# HLD-stat-tracker-bottom.net
KiCad netlist of a schematic drawn in EAGLE
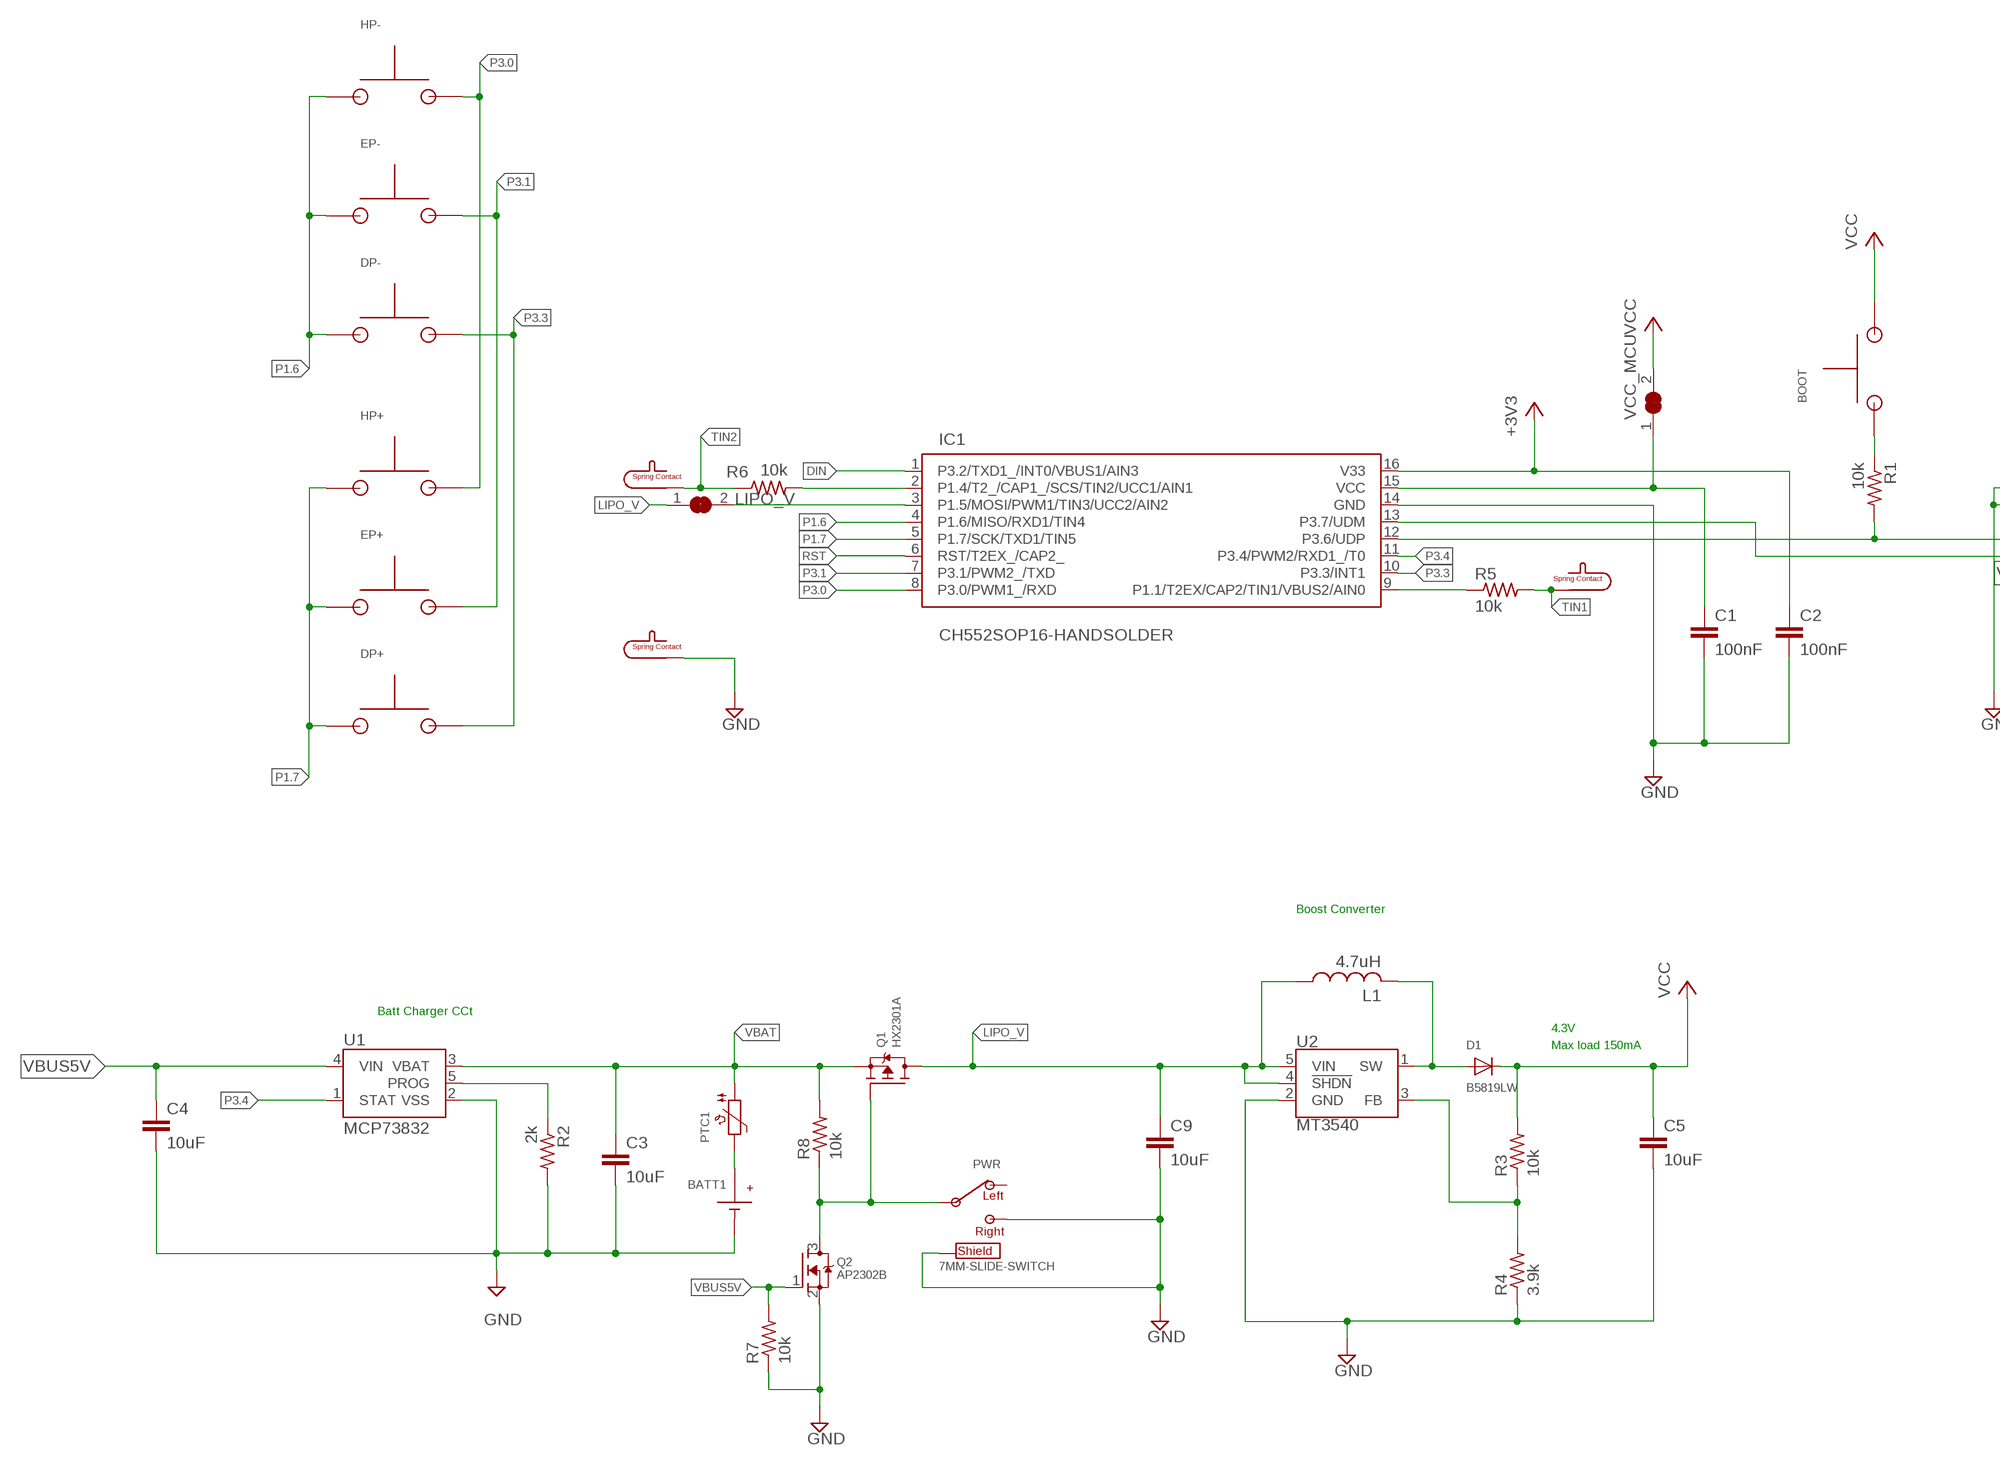
[diagram p0: schematic, sheet 1, part 1 of 2]
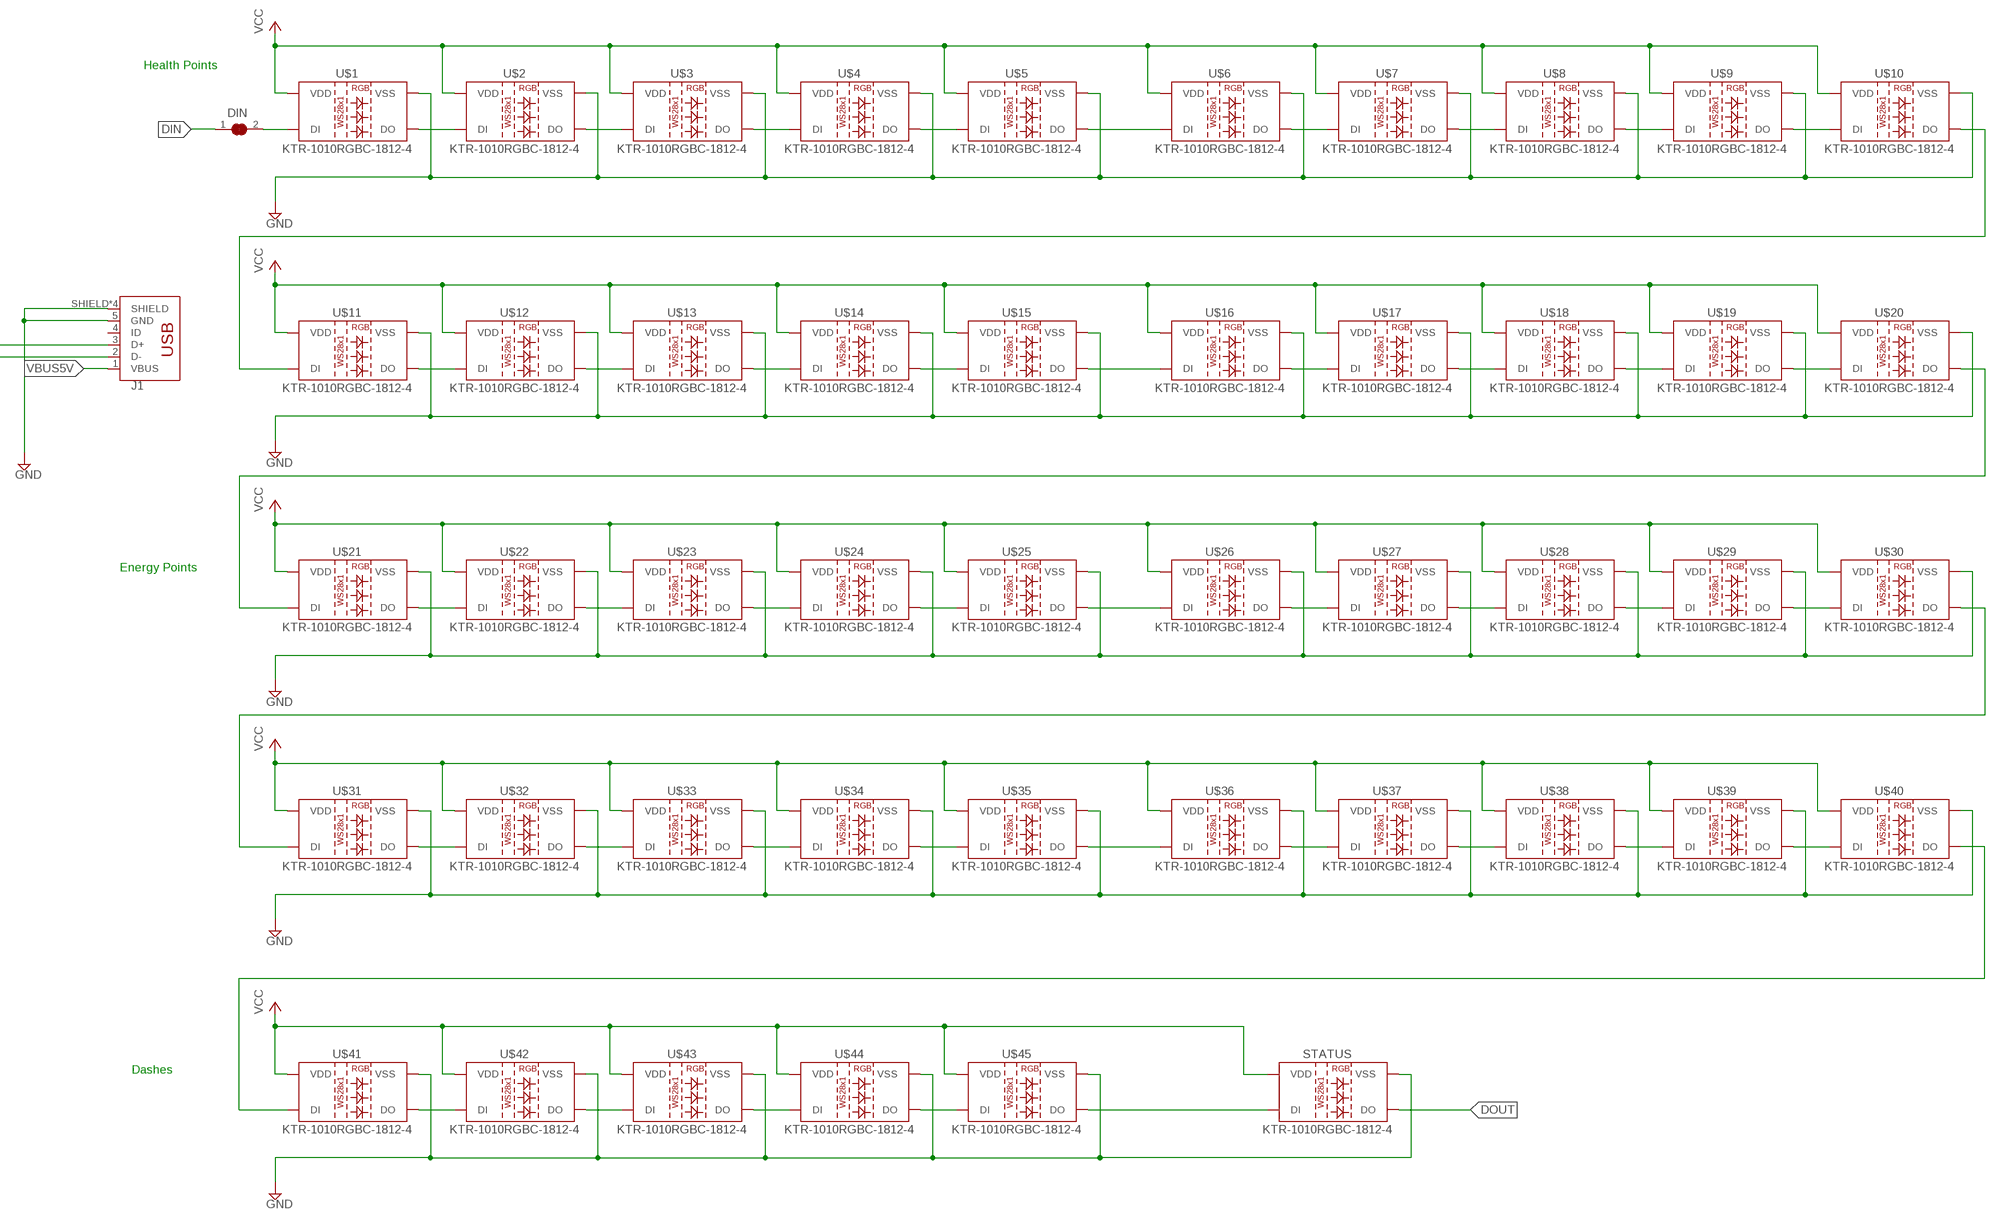
[diagram p1: schematic, sheet 1, part 2 of 2]

(export (version "E")
  (design (tool "Eeschema 10.0.6"))
  (components
    (comp (ref "BATT1")
      (value "BATT+")
      (footprint "eagle-import:BATT+PAD")
      (fields (field (name "PARTNO") "?"))
      (libsource (lib "eagle-import") (part "BATT+"))
    )
    (comp (ref "BATT1-")
      (value "BATT-")
      (footprint "eagle-import:BATT-PAD")
      (fields (field (name "PARTNO") "?"))
      (libsource (lib "eagle-import") (part "BATT-"))
    )
    (comp (ref "BOOT")
      (value "TACTSW")
      (footprint "eagle-import:3MM-TACT")
      (fields (field (name "MANUFACTURER") "SHOU HAN") (field (name "PARTNO") "TS3315A"))
      (libsource (lib "eagle-import") (part "TACTSW"))
    )
    (comp (ref "C1")
      (value "100nF")
      (footprint "eagle-import:C0805K")
      (fields (field (name "PARTNO") "?"))
      (libsource (lib "eagle-import") (part "C-EUC0805K"))
    )
    (comp (ref "C2")
      (value "100nF")
      (footprint "eagle-import:C0805K")
      (fields (field (name "PARTNO") "?"))
      (libsource (lib "eagle-import") (part "C-EUC0805K"))
    )
    (comp (ref "C3")
      (value "10uF")
      (footprint "eagle-import:C0805K")
      (fields (field (name "PARTNO") "?"))
      (libsource (lib "eagle-import") (part "C-EUC0805K"))
    )
    (comp (ref "C4")
      (value "10uF")
      (footprint "eagle-import:C0805K")
      (fields (field (name "PARTNO") "?"))
      (libsource (lib "eagle-import") (part "C-EUC0805K"))
    )
    (comp (ref "C5")
      (value "10uF")
      (footprint "eagle-import:C0805K")
      (fields (field (name "PARTNO") "?"))
      (libsource (lib "eagle-import") (part "C-EUC0805K"))
    )
    (comp (ref "C9")
      (value "10uF")
      (footprint "eagle-import:C0805K")
      (fields (field (name "PARTNO") "?"))
      (libsource (lib "eagle-import") (part "C-EUC0805K"))
    )
    (comp (ref "D1")
      (value "B5819LW")
      (footprint "eagle-import:SOD-123")
      (fields (field (name "MANUFACTURER") "Guangdong Hottech ") (field (name "PARTNO") "B5819LW "))
      (libsource (lib "eagle-import") (part "DIODESOD-123"))
    )
    (comp (ref "DIN")
      (value "SOLDERJUMPER-NC")
      (footprint "eagle-import:SOLDERJUMPER_CLOSEDWIRE_SMALL")
      (libsource (lib "eagle-import") (part "SOLDERJUMPER-NC"))
    )
    (comp (ref "DP+")
      (value "TACTSW")
      (footprint "eagle-import:3MM-TACT")
      (fields (field (name "MANUFACTURER") "SHOU HAN") (field (name "PARTNO") "TS3315A"))
      (libsource (lib "eagle-import") (part "TACTSW"))
    )
    (comp (ref "DP-")
      (value "TACTSW")
      (footprint "eagle-import:3MM-TACT")
      (fields (field (name "MANUFACTURER") "SHOU HAN") (field (name "PARTNO") "TS3315A"))
      (libsource (lib "eagle-import") (part "TACTSW"))
    )
    (comp (ref "EP+")
      (value "TACTSW")
      (footprint "eagle-import:3MM-TACT")
      (fields (field (name "MANUFACTURER") "SHOU HAN") (field (name "PARTNO") "TS3315A"))
      (libsource (lib "eagle-import") (part "TACTSW"))
    )
    (comp (ref "EP-")
      (value "TACTSW")
      (footprint "eagle-import:3MM-TACT")
      (fields (field (name "MANUFACTURER") "SHOU HAN") (field (name "PARTNO") "TS3315A"))
      (libsource (lib "eagle-import") (part "TACTSW"))
    )
    (comp (ref "GND")
      (value "SPRING-CONTACT")
      (footprint "eagle-import:818000905-SPRING-CONTACT")
      (fields (field (name "MANUFACTURER") "ECT") (field (name "PARTNO") "ECT818000905"))
      (libsource (lib "eagle-import") (part "SPRING-CONTACT"))
    )
    (comp (ref "HP+")
      (value "TACTSW")
      (footprint "eagle-import:3MM-TACT")
      (fields (field (name "MANUFACTURER") "SHOU HAN") (field (name "PARTNO") "TS3315A"))
      (libsource (lib "eagle-import") (part "TACTSW"))
    )
    (comp (ref "HP-")
      (value "TACTSW")
      (footprint "eagle-import:3MM-TACT")
      (fields
        (field (name "MANUFACTURER") "SHOU HAN")
        (field (name "PARTNO") "TS3315A")
        (field (name "MANUFACTURER_1") "SHOU HAN")
        (field (name "PARTNO_1") "TS3315A")
      )
      (libsource (lib "eagle-import") (part "TACTSW"))
    )
    (comp (ref "IC1")
      (value "CH552SOP16-HANDSOLDER")
      (footprint "eagle-import:SOP16-HANDSOLDER")
      (fields (field (name "MANUFACTURER") "WCH(Jiangsu Qin Heng)") (field (name "PARTNO") "CH552G"))
      (libsource (lib "eagle-import") (part "CH552SOP16-HANDSOLDER"))
    )
    (comp (ref "J1")
      (value "USB_MICRO-BSINK-PLATE")
      (footprint "eagle-import:USB-B-MICRO-SMD-SINK-PLATE")
      (fields
        (field (name "MANUFACTURER") "Jing Extension of the Electronic Co. ")
        (field (name "PARTNO") "C40957")
      )
      (libsource (lib "eagle-import") (part "USB_MICRO-BSINK-PLATE"))
    )
    (comp (ref "L1")
      (value "4.7uH")
      (footprint "eagle-import:BEADC2012X105N")
      (fields (field (name "MANUFACTURER") "INPAQ") (field (name "PARTNO") "C315723"))
      (libsource (lib "eagle-import") (part "INDUCTOR2012"))
    )
    (comp (ref "LIPO_V")
      (value "SOLDERJUMPER-NC")
      (footprint "eagle-import:SOLDERJUMPER_CLOSEDWIRE_SMALL")
      (libsource (lib "eagle-import") (part "SOLDERJUMPER-NC"))
    )
    (comp (ref "PTC1")
      (value "PTC0805")
      (footprint "eagle-import:WCAP-CSGP_0805_H1.25_R")
      (fields
        (field (name "MANUFACTURER") "  Jinrui Electronic Materials Co.")
        (field (name "PARTNO") "JK-SMD0805-075")
      )
      (libsource (lib "eagle-import") (part "PTC0805"))
    )
    (comp (ref "PWR")
      (value "7MM-SLIDE-SWITCH")
      (footprint "eagle-import:7MM-SMD-SLIDE-SWITCH")
      (fields (field (name "MANUFACTURER") "XKB Enterprise") (field (name "PARTNO") "SK-3296S-01-L1 "))
      (libsource (lib "eagle-import") (part "7MM-SLIDE-SWITCH"))
    )
    (comp (ref "Q1")
      (value "HX2301A")
      (footprint "eagle-import:SOT23-R")
      (fields (field (name "MANUFACTURER") "HX(hengjiaxing) ") (field (name "PARTNO") "HX2301A "))
      (libsource (lib "eagle-import") (part "MOSFET-P"))
    )
    (comp (ref "Q2")
      (value "AP2302B")
      (footprint "eagle-import:SOT23-R")
      (fields (field (name "MANUFACTURER") "HX(hengjiaxing)"))
      (libsource (lib "eagle-import") (part "MOSFET-NREFLOW"))
    )
    (comp (ref "R1")
      (value "10k")
      (footprint "eagle-import:R0805S")
      (fields (field (name "PARTNO") "?"))
      (libsource (lib "eagle-import") (part "R-US_R0805S"))
    )
    (comp (ref "R2")
      (value "2k")
      (footprint "eagle-import:R0805S")
      (fields (field (name "PARTNO") "?"))
      (libsource (lib "eagle-import") (part "R-US_R0805S"))
    )
    (comp (ref "R3")
      (value "10k")
      (footprint "eagle-import:R0805S")
      (fields (field (name "PARTNO") "?"))
      (libsource (lib "eagle-import") (part "R-US_R0805S"))
    )
    (comp (ref "R4")
      (value "3.9k")
      (footprint "eagle-import:R0805S")
      (fields (field (name "PARTNO") "?"))
      (libsource (lib "eagle-import") (part "R-US_R0805S"))
    )
    (comp (ref "R5")
      (value "10k")
      (footprint "eagle-import:R0805S")
      (fields (field (name "PARTNO") "?"))
      (libsource (lib "eagle-import") (part "R-US_R0805S"))
    )
    (comp (ref "R6")
      (value "10k")
      (footprint "eagle-import:R0805S")
      (fields (field (name "PARTNO") "?"))
      (libsource (lib "eagle-import") (part "R-US_R0805S"))
    )
    (comp (ref "R7")
      (value "10k")
      (footprint "eagle-import:R0805S")
      (fields (field (name "PARTNO") "?"))
      (libsource (lib "eagle-import") (part "R-US_R0805S"))
    )
    (comp (ref "R8")
      (value "10k")
      (footprint "eagle-import:R0805S")
      (fields (field (name "PARTNO") "?"))
      (libsource (lib "eagle-import") (part "R-US_R0805S"))
    )
    (comp (ref "STATUS")
      (value "KTR-1010RGBC-1812-4")
      (footprint "eagle-import:SK6812-2020")
      (fields (field (name "MANUFACTURER") "KTRLIGHT"))
      (libsource (lib "eagle-import") (part "KTR-1010RGBC-1812-4"))
    )
    (comp (ref "TIN1")
      (value "SPRING-CONTACT")
      (footprint "eagle-import:818000905-SPRING-CONTACT")
      (fields (field (name "MANUFACTURER") "ECT") (field (name "PARTNO") "ECT818000905"))
      (libsource (lib "eagle-import") (part "SPRING-CONTACT"))
    )
    (comp (ref "TIN2")
      (value "SPRING-CONTACT")
      (footprint "eagle-import:818000905-SPRING-CONTACT")
      (fields (field (name "MANUFACTURER") "ECT") (field (name "PARTNO") "ECT818000905"))
      (libsource (lib "eagle-import") (part "SPRING-CONTACT"))
    )
    (comp (ref "U$1")
      (value "KTR-1010RGBC-1812-4")
      (footprint "eagle-import:SK6812-2020")
      (fields (field (name "MANUFACTURER") "KTRLIGHT"))
      (libsource (lib "eagle-import") (part "KTR-1010RGBC-1812-4"))
    )
    (comp (ref "U$2")
      (value "KTR-1010RGBC-1812-4")
      (footprint "eagle-import:SK6812-2020")
      (fields (field (name "MANUFACTURER") "KTRLIGHT"))
      (libsource (lib "eagle-import") (part "KTR-1010RGBC-1812-4"))
    )
    (comp (ref "U$3")
      (value "KTR-1010RGBC-1812-4")
      (footprint "eagle-import:SK6812-2020")
      (fields (field (name "MANUFACTURER") "KTRLIGHT"))
      (libsource (lib "eagle-import") (part "KTR-1010RGBC-1812-4"))
    )
    (comp (ref "U$4")
      (value "KTR-1010RGBC-1812-4")
      (footprint "eagle-import:SK6812-2020")
      (fields (field (name "MANUFACTURER") "KTRLIGHT"))
      (libsource (lib "eagle-import") (part "KTR-1010RGBC-1812-4"))
    )
    (comp (ref "U$5")
      (value "KTR-1010RGBC-1812-4")
      (footprint "eagle-import:SK6812-2020")
      (fields (field (name "MANUFACTURER") "KTRLIGHT"))
      (libsource (lib "eagle-import") (part "KTR-1010RGBC-1812-4"))
    )
    (comp (ref "U$6")
      (value "KTR-1010RGBC-1812-4")
      (footprint "eagle-import:SK6812-2020")
      (fields (field (name "MANUFACTURER") "KTRLIGHT"))
      (libsource (lib "eagle-import") (part "KTR-1010RGBC-1812-4"))
    )
    (comp (ref "U$7")
      (value "KTR-1010RGBC-1812-4")
      (footprint "eagle-import:SK6812-2020")
      (fields (field (name "MANUFACTURER") "KTRLIGHT"))
      (libsource (lib "eagle-import") (part "KTR-1010RGBC-1812-4"))
    )
    (comp (ref "U$8")
      (value "KTR-1010RGBC-1812-4")
      (footprint "eagle-import:SK6812-2020")
      (fields (field (name "MANUFACTURER") "KTRLIGHT"))
      (libsource (lib "eagle-import") (part "KTR-1010RGBC-1812-4"))
    )
    (comp (ref "U$9")
      (value "KTR-1010RGBC-1812-4")
      (footprint "eagle-import:SK6812-2020")
      (fields (field (name "MANUFACTURER") "KTRLIGHT"))
      (libsource (lib "eagle-import") (part "KTR-1010RGBC-1812-4"))
    )
    (comp (ref "U$10")
      (value "KTR-1010RGBC-1812-4")
      (footprint "eagle-import:SK6812-2020")
      (fields (field (name "MANUFACTURER") "KTRLIGHT"))
      (libsource (lib "eagle-import") (part "KTR-1010RGBC-1812-4"))
    )
    (comp (ref "U$11")
      (value "KTR-1010RGBC-1812-4")
      (footprint "eagle-import:SK6812-2020")
      (fields (field (name "MANUFACTURER") "KTRLIGHT"))
      (libsource (lib "eagle-import") (part "KTR-1010RGBC-1812-4"))
    )
    (comp (ref "U$12")
      (value "KTR-1010RGBC-1812-4")
      (footprint "eagle-import:SK6812-2020")
      (fields (field (name "MANUFACTURER") "KTRLIGHT"))
      (libsource (lib "eagle-import") (part "KTR-1010RGBC-1812-4"))
    )
    (comp (ref "U$13")
      (value "KTR-1010RGBC-1812-4")
      (footprint "eagle-import:SK6812-2020")
      (fields (field (name "MANUFACTURER") "KTRLIGHT"))
      (libsource (lib "eagle-import") (part "KTR-1010RGBC-1812-4"))
    )
    (comp (ref "U$14")
      (value "KTR-1010RGBC-1812-4")
      (footprint "eagle-import:SK6812-2020")
      (fields (field (name "MANUFACTURER") "KTRLIGHT"))
      (libsource (lib "eagle-import") (part "KTR-1010RGBC-1812-4"))
    )
    (comp (ref "U$15")
      (value "KTR-1010RGBC-1812-4")
      (footprint "eagle-import:SK6812-2020")
      (fields (field (name "MANUFACTURER") "KTRLIGHT"))
      (libsource (lib "eagle-import") (part "KTR-1010RGBC-1812-4"))
    )
    (comp (ref "U$16")
      (value "KTR-1010RGBC-1812-4")
      (footprint "eagle-import:SK6812-2020")
      (fields (field (name "MANUFACTURER") "KTRLIGHT"))
      (libsource (lib "eagle-import") (part "KTR-1010RGBC-1812-4"))
    )
    (comp (ref "U$17")
      (value "KTR-1010RGBC-1812-4")
      (footprint "eagle-import:SK6812-2020")
      (fields (field (name "MANUFACTURER") "KTRLIGHT"))
      (libsource (lib "eagle-import") (part "KTR-1010RGBC-1812-4"))
    )
    (comp (ref "U$18")
      (value "KTR-1010RGBC-1812-4")
      (footprint "eagle-import:SK6812-2020")
      (fields (field (name "MANUFACTURER") "KTRLIGHT"))
      (libsource (lib "eagle-import") (part "KTR-1010RGBC-1812-4"))
    )
    (comp (ref "U$19")
      (value "KTR-1010RGBC-1812-4")
      (footprint "eagle-import:SK6812-2020")
      (fields (field (name "MANUFACTURER") "KTRLIGHT"))
      (libsource (lib "eagle-import") (part "KTR-1010RGBC-1812-4"))
    )
    (comp (ref "U$20")
      (value "KTR-1010RGBC-1812-4")
      (footprint "eagle-import:SK6812-2020")
      (fields (field (name "MANUFACTURER") "KTRLIGHT"))
      (libsource (lib "eagle-import") (part "KTR-1010RGBC-1812-4"))
    )
    (comp (ref "U$21")
      (value "KTR-1010RGBC-1812-4")
      (footprint "eagle-import:SK6812-2020")
      (fields (field (name "MANUFACTURER") "KTRLIGHT"))
      (libsource (lib "eagle-import") (part "KTR-1010RGBC-1812-4"))
    )
    (comp (ref "U$22")
      (value "KTR-1010RGBC-1812-4")
      (footprint "eagle-import:SK6812-2020")
      (fields (field (name "MANUFACTURER") "KTRLIGHT"))
      (libsource (lib "eagle-import") (part "KTR-1010RGBC-1812-4"))
    )
    (comp (ref "U$23")
      (value "KTR-1010RGBC-1812-4")
      (footprint "eagle-import:SK6812-2020")
      (fields (field (name "MANUFACTURER") "KTRLIGHT"))
      (libsource (lib "eagle-import") (part "KTR-1010RGBC-1812-4"))
    )
    (comp (ref "U$24")
      (value "KTR-1010RGBC-1812-4")
      (footprint "eagle-import:SK6812-2020")
      (fields (field (name "MANUFACTURER") "KTRLIGHT"))
      (libsource (lib "eagle-import") (part "KTR-1010RGBC-1812-4"))
    )
    (comp (ref "U$25")
      (value "KTR-1010RGBC-1812-4")
      (footprint "eagle-import:SK6812-2020")
      (fields (field (name "MANUFACTURER") "KTRLIGHT"))
      (libsource (lib "eagle-import") (part "KTR-1010RGBC-1812-4"))
    )
    (comp (ref "U$26")
      (value "KTR-1010RGBC-1812-4")
      (footprint "eagle-import:SK6812-2020")
      (fields (field (name "MANUFACTURER") "KTRLIGHT"))
      (libsource (lib "eagle-import") (part "KTR-1010RGBC-1812-4"))
    )
    (comp (ref "U$27")
      (value "KTR-1010RGBC-1812-4")
      (footprint "eagle-import:SK6812-2020")
      (fields (field (name "MANUFACTURER") "KTRLIGHT"))
      (libsource (lib "eagle-import") (part "KTR-1010RGBC-1812-4"))
    )
    (comp (ref "U$28")
      (value "KTR-1010RGBC-1812-4")
      (footprint "eagle-import:SK6812-2020")
      (fields (field (name "MANUFACTURER") "KTRLIGHT"))
      (libsource (lib "eagle-import") (part "KTR-1010RGBC-1812-4"))
    )
    (comp (ref "U$29")
      (value "KTR-1010RGBC-1812-4")
      (footprint "eagle-import:SK6812-2020")
      (fields (field (name "MANUFACTURER") "KTRLIGHT"))
      (libsource (lib "eagle-import") (part "KTR-1010RGBC-1812-4"))
    )
    (comp (ref "U$30")
      (value "KTR-1010RGBC-1812-4")
      (footprint "eagle-import:SK6812-2020")
      (fields (field (name "MANUFACTURER") "KTRLIGHT"))
      (libsource (lib "eagle-import") (part "KTR-1010RGBC-1812-4"))
    )
    (comp (ref "U$31")
      (value "KTR-1010RGBC-1812-4")
      (footprint "eagle-import:SK6812-2020")
      (fields (field (name "MANUFACTURER") "KTRLIGHT"))
      (libsource (lib "eagle-import") (part "KTR-1010RGBC-1812-4"))
    )
    (comp (ref "U$32")
      (value "KTR-1010RGBC-1812-4")
      (footprint "eagle-import:SK6812-2020")
      (fields (field (name "MANUFACTURER") "KTRLIGHT"))
      (libsource (lib "eagle-import") (part "KTR-1010RGBC-1812-4"))
    )
    (comp (ref "U$33")
      (value "KTR-1010RGBC-1812-4")
      (footprint "eagle-import:SK6812-2020")
      (fields (field (name "MANUFACTURER") "KTRLIGHT"))
      (libsource (lib "eagle-import") (part "KTR-1010RGBC-1812-4"))
    )
    (comp (ref "U$34")
      (value "KTR-1010RGBC-1812-4")
      (footprint "eagle-import:SK6812-2020")
      (fields (field (name "MANUFACTURER") "KTRLIGHT"))
      (libsource (lib "eagle-import") (part "KTR-1010RGBC-1812-4"))
    )
    (comp (ref "U$35")
      (value "KTR-1010RGBC-1812-4")
      (footprint "eagle-import:SK6812-2020")
      (fields (field (name "MANUFACTURER") "KTRLIGHT"))
      (libsource (lib "eagle-import") (part "KTR-1010RGBC-1812-4"))
    )
    (comp (ref "U$36")
      (value "KTR-1010RGBC-1812-4")
      (footprint "eagle-import:SK6812-2020")
      (fields (field (name "MANUFACTURER") "KTRLIGHT"))
      (libsource (lib "eagle-import") (part "KTR-1010RGBC-1812-4"))
    )
    (comp (ref "U$37")
      (value "KTR-1010RGBC-1812-4")
      (footprint "eagle-import:SK6812-2020")
      (fields (field (name "MANUFACTURER") "KTRLIGHT"))
      (libsource (lib "eagle-import") (part "KTR-1010RGBC-1812-4"))
    )
    (comp (ref "U$38")
      (value "KTR-1010RGBC-1812-4")
      (footprint "eagle-import:SK6812-2020")
      (fields (field (name "MANUFACTURER") "KTRLIGHT"))
      (libsource (lib "eagle-import") (part "KTR-1010RGBC-1812-4"))
    )
    (comp (ref "U$39")
      (value "KTR-1010RGBC-1812-4")
      (footprint "eagle-import:SK6812-2020")
      (fields (field (name "MANUFACTURER") "KTRLIGHT"))
      (libsource (lib "eagle-import") (part "KTR-1010RGBC-1812-4"))
    )
    (comp (ref "U$40")
      (value "KTR-1010RGBC-1812-4")
      (footprint "eagle-import:SK6812-2020")
      (fields (field (name "MANUFACTURER") "KTRLIGHT"))
      (libsource (lib "eagle-import") (part "KTR-1010RGBC-1812-4"))
    )
    (comp (ref "U$41")
      (value "KTR-1010RGBC-1812-4")
      (footprint "eagle-import:SK6812-2020")
      (fields (field (name "MANUFACTURER") "KTRLIGHT"))
      (libsource (lib "eagle-import") (part "KTR-1010RGBC-1812-4"))
    )
    (comp (ref "U$42")
      (value "KTR-1010RGBC-1812-4")
      (footprint "eagle-import:SK6812-2020")
      (fields (field (name "MANUFACTURER") "KTRLIGHT"))
      (libsource (lib "eagle-import") (part "KTR-1010RGBC-1812-4"))
    )
    (comp (ref "U$43")
      (value "KTR-1010RGBC-1812-4")
      (footprint "eagle-import:SK6812-2020")
      (fields (field (name "MANUFACTURER") "KTRLIGHT"))
      (libsource (lib "eagle-import") (part "KTR-1010RGBC-1812-4"))
    )
    (comp (ref "U$44")
      (value "KTR-1010RGBC-1812-4")
      (footprint "eagle-import:SK6812-2020")
      (fields (field (name "MANUFACTURER") "KTRLIGHT"))
      (libsource (lib "eagle-import") (part "KTR-1010RGBC-1812-4"))
    )
    (comp (ref "U$45")
      (value "KTR-1010RGBC-1812-4")
      (footprint "eagle-import:SK6812-2020")
      (fields (field (name "MANUFACTURER") "KTRLIGHT"))
      (libsource (lib "eagle-import") (part "KTR-1010RGBC-1812-4"))
    )
    (comp (ref "U1")
      (value "MCP73832")
      (footprint "eagle-import:SOT23-5")
      (fields (field (name "MANUFACTURER") "Microchip Tech"))
      (libsource (lib "eagle-import") (part "MCP73831"))
    )
    (comp (ref "U2")
      (value "MT3540")
      (footprint "eagle-import:SOT23-5")
      (fields (field (name "MANUFACTURER") "XI'AN Aerosemi Tech") (field (name "PARTNO") "MT3540 "))
      (libsource (lib "eagle-import") (part "AP3012"))
    )
    (comp (ref "VCC_MCU")
      (value "SOLDERJUMPER-NC")
      (footprint "eagle-import:SOLDERJUMPER_CLOSEDWIRE_SMALL")
      (libsource (lib "eagle-import") (part "SOLDERJUMPER-NC"))
    )
  )
  (nets
    (net (code "1") (name "+3V3") (class "Default")
      (node (ref "C2") (pin "1") (pinfunction "1_1") (pintype "passive"))
      (node (ref "IC1") (pin "16") (pinfunction "V33_16") (pintype "bidirectional"))
    )
    (net (code "2") (name "DIN") (class "Default")
      (node (ref "DIN") (pin "1") (pinfunction "1_1") (pintype "passive"))
      (node (ref "IC1") (pin "1") (pinfunction "P3.2/TXD1_/INT0/VBUS1/AIN3_1") (pintype "bidirectional"))
    )
    (net (code "3") (name "DOUT") (class "Default")
      (node (ref "STATUS") (pin "DOUT") (pinfunction "DO_DOUT") (pintype "bidirectional"))
    )
    (net (code "4") (name "GND") (class "Default")
      (node (ref "BATT1-") (pin "P$1") (pinfunction "BATT-_P$1") (pintype "bidirectional"))
      (node (ref "C1") (pin "2") (pinfunction "2_2") (pintype "passive"))
      (node (ref "C2") (pin "2") (pinfunction "2_2") (pintype "passive"))
      (node (ref "C3") (pin "2") (pinfunction "2_2") (pintype "passive"))
      (node (ref "C4") (pin "2") (pinfunction "2_2") (pintype "passive"))
      (node (ref "C5") (pin "2") (pinfunction "2_2") (pintype "passive"))
      (node (ref "C9") (pin "2") (pinfunction "2_2") (pintype "passive"))
      (node (ref "GND") (pin "P$1") (pinfunction "P$1_P$1") (pintype "bidirectional"))
      (node (ref "IC1") (pin "14") (pinfunction "GND_14") (pintype "bidirectional"))
      (node (ref "J1") (pin "5") (pinfunction "GND_5") (pintype "power_in"))
      (node (ref "J1") (pin "SHIELD") (pinfunction "SHIELD_SHIELD") (pintype "bidirectional"))
      (node (ref "J1") (pin "SHIELD2") (pinfunction "SHIELD_SHIELD2") (pintype "bidirectional"))
      (node (ref "J1") (pin "SHIELD3") (pinfunction "SHIELD_SHIELD3") (pintype "bidirectional"))
      (node (ref "J1") (pin "SHIELD4") (pinfunction "SHIELD_SHIELD4") (pintype "bidirectional"))
      (node (ref "PWR") (pin "3") (pinfunction "P$3_3") (pintype "passive"))
      (node (ref "PWR") (pin "GND@1") (pinfunction "SHIELD_GND@1") (pintype "passive"))
      (node (ref "PWR") (pin "GND@2") (pinfunction "SHIELD_GND@2") (pintype "passive"))
      (node (ref "PWR") (pin "GND@3") (pinfunction "SHIELD_GND@3") (pintype "passive"))
      (node (ref "PWR") (pin "GND@4") (pinfunction "SHIELD_GND@4") (pintype "passive"))
      (node (ref "Q2") (pin "2") (pinfunction "S_2") (pintype "bidirectional"))
      (node (ref "R2") (pin "2") (pinfunction "2_2") (pintype "passive"))
      (node (ref "R4") (pin "1") (pinfunction "1_1") (pintype "passive"))
      (node (ref "R7") (pin "1") (pinfunction "1_1") (pintype "passive"))
      (node (ref "STATUS") (pin "VSS") (pinfunction "VSS_VSS") (pintype "bidirectional"))
      (node (ref "U$1") (pin "VSS") (pinfunction "VSS_VSS") (pintype "bidirectional"))
      (node (ref "U$10") (pin "VSS") (pinfunction "VSS_VSS") (pintype "bidirectional"))
      (node (ref "U$11") (pin "VSS") (pinfunction "VSS_VSS") (pintype "bidirectional"))
      (node (ref "U$12") (pin "VSS") (pinfunction "VSS_VSS") (pintype "bidirectional"))
      (node (ref "U$13") (pin "VSS") (pinfunction "VSS_VSS") (pintype "bidirectional"))
      (node (ref "U$14") (pin "VSS") (pinfunction "VSS_VSS") (pintype "bidirectional"))
      (node (ref "U$15") (pin "VSS") (pinfunction "VSS_VSS") (pintype "bidirectional"))
      (node (ref "U$16") (pin "VSS") (pinfunction "VSS_VSS") (pintype "bidirectional"))
      (node (ref "U$17") (pin "VSS") (pinfunction "VSS_VSS") (pintype "bidirectional"))
      (node (ref "U$18") (pin "VSS") (pinfunction "VSS_VSS") (pintype "bidirectional"))
      (node (ref "U$19") (pin "VSS") (pinfunction "VSS_VSS") (pintype "bidirectional"))
      (node (ref "U$2") (pin "VSS") (pinfunction "VSS_VSS") (pintype "bidirectional"))
      (node (ref "U$20") (pin "VSS") (pinfunction "VSS_VSS") (pintype "bidirectional"))
      (node (ref "U$21") (pin "VSS") (pinfunction "VSS_VSS") (pintype "bidirectional"))
      (node (ref "U$22") (pin "VSS") (pinfunction "VSS_VSS") (pintype "bidirectional"))
      (node (ref "U$23") (pin "VSS") (pinfunction "VSS_VSS") (pintype "bidirectional"))
      (node (ref "U$24") (pin "VSS") (pinfunction "VSS_VSS") (pintype "bidirectional"))
      (node (ref "U$25") (pin "VSS") (pinfunction "VSS_VSS") (pintype "bidirectional"))
      (node (ref "U$26") (pin "VSS") (pinfunction "VSS_VSS") (pintype "bidirectional"))
      (node (ref "U$27") (pin "VSS") (pinfunction "VSS_VSS") (pintype "bidirectional"))
      (node (ref "U$28") (pin "VSS") (pinfunction "VSS_VSS") (pintype "bidirectional"))
      (node (ref "U$29") (pin "VSS") (pinfunction "VSS_VSS") (pintype "bidirectional"))
      (node (ref "U$3") (pin "VSS") (pinfunction "VSS_VSS") (pintype "bidirectional"))
      (node (ref "U$30") (pin "VSS") (pinfunction "VSS_VSS") (pintype "bidirectional"))
      (node (ref "U$31") (pin "VSS") (pinfunction "VSS_VSS") (pintype "bidirectional"))
      (node (ref "U$32") (pin "VSS") (pinfunction "VSS_VSS") (pintype "bidirectional"))
      (node (ref "U$33") (pin "VSS") (pinfunction "VSS_VSS") (pintype "bidirectional"))
      (node (ref "U$34") (pin "VSS") (pinfunction "VSS_VSS") (pintype "bidirectional"))
      (node (ref "U$35") (pin "VSS") (pinfunction "VSS_VSS") (pintype "bidirectional"))
      (node (ref "U$36") (pin "VSS") (pinfunction "VSS_VSS") (pintype "bidirectional"))
      (node (ref "U$37") (pin "VSS") (pinfunction "VSS_VSS") (pintype "bidirectional"))
      (node (ref "U$38") (pin "VSS") (pinfunction "VSS_VSS") (pintype "bidirectional"))
      (node (ref "U$39") (pin "VSS") (pinfunction "VSS_VSS") (pintype "bidirectional"))
      (node (ref "U$4") (pin "VSS") (pinfunction "VSS_VSS") (pintype "bidirectional"))
      (node (ref "U$40") (pin "VSS") (pinfunction "VSS_VSS") (pintype "bidirectional"))
      (node (ref "U$41") (pin "VSS") (pinfunction "VSS_VSS") (pintype "bidirectional"))
      (node (ref "U$42") (pin "VSS") (pinfunction "VSS_VSS") (pintype "bidirectional"))
      (node (ref "U$43") (pin "VSS") (pinfunction "VSS_VSS") (pintype "bidirectional"))
      (node (ref "U$44") (pin "VSS") (pinfunction "VSS_VSS") (pintype "bidirectional"))
      (node (ref "U$45") (pin "VSS") (pinfunction "VSS_VSS") (pintype "bidirectional"))
      (node (ref "U$5") (pin "VSS") (pinfunction "VSS_VSS") (pintype "bidirectional"))
      (node (ref "U$6") (pin "VSS") (pinfunction "VSS_VSS") (pintype "bidirectional"))
      (node (ref "U$7") (pin "VSS") (pinfunction "VSS_VSS") (pintype "bidirectional"))
      (node (ref "U$8") (pin "VSS") (pinfunction "VSS_VSS") (pintype "bidirectional"))
      (node (ref "U$9") (pin "VSS") (pinfunction "VSS_VSS") (pintype "bidirectional"))
      (node (ref "U1") (pin "2") (pinfunction "VSS_2") (pintype "power_in"))
      (node (ref "U2") (pin "2") (pinfunction "GND_2") (pintype "bidirectional"))
    )
    (net (code "5") (name "LIPO_V") (class "Default")
      (node (ref "C9") (pin "1") (pinfunction "1_1") (pintype "passive"))
      (node (ref "L1") (pin "1") (pinfunction "1_1") (pintype "passive"))
      (node (ref "LIPO_V") (pin "1") (pinfunction "1_1") (pintype "passive"))
      (node (ref "Q1") (pin "3") (pinfunction "D_3") (pintype "passive"))
      (node (ref "U2") (pin "4") (pinfunction "~{SHDN}_4") (pintype "bidirectional"))
      (node (ref "U2") (pin "5") (pinfunction "VIN_5") (pintype "bidirectional"))
    )
    (net (code "6") (name "Net-(BATT1-BATT+)") (class "Default")
      (node (ref "BATT1") (pin "P$1") (pinfunction "BATT+_P$1") (pintype "bidirectional"))
      (node (ref "PTC1") (pin "2") (pinfunction "2_2") (pintype "passive"))
    )
    (net (code "7") (name "Net-(BOOT-P$1-Pad1)") (class "Default")
      (node (ref "BOOT") (pin "1") (pinfunction "P$1_1") (pintype "bidirectional"))
      (node (ref "BOOT") (pin "2") (pinfunction "P$1_2") (pintype "bidirectional"))
      (node (ref "R1") (pin "1") (pinfunction "1_1") (pintype "passive"))
    )
    (net (code "8") (name "Net-(IC1-P1.1{slash}T2EX{slash}CAP2{slash}TIN1{slash}VBUS2{slash}AIN0)") (class "Default")
      (node (ref "IC1") (pin "9") (pinfunction "P1.1/T2EX/CAP2/TIN1/VBUS2/AIN0_9") (pintype "bidirectional"))
      (node (ref "R5") (pin "1") (pinfunction "1_1") (pintype "passive"))
    )
    (net (code "9") (name "Net-(IC1-P1.4{slash}T2_{slash}CAP1_{slash}SCS{slash}TIN2{slash}UCC1{slash}AIN1)") (class "Default")
      (node (ref "IC1") (pin "2") (pinfunction "P1.4/T2_/CAP1_/SCS/TIN2/UCC1/AIN1_2") (pintype "bidirectional"))
      (node (ref "R6") (pin "2") (pinfunction "2_2") (pintype "passive"))
    )
    (net (code "10") (name "Net-(IC1-P1.5{slash}MOSI{slash}PWM1{slash}TIN3{slash}UCC2{slash}AIN2)") (class "Default")
      (node (ref "IC1") (pin "3") (pinfunction "P1.5/MOSI/PWM1/TIN3/UCC2/AIN2_3") (pintype "bidirectional"))
      (node (ref "LIPO_V") (pin "2") (pinfunction "2_2") (pintype "passive"))
    )
    (net (code "11") (name "Net-(IC1-P3.6{slash}UDP)") (class "Default")
      (node (ref "IC1") (pin "12") (pinfunction "P3.6/UDP_12") (pintype "bidirectional"))
      (node (ref "J1") (pin "3") (pinfunction "D+_3") (pintype "bidirectional"))
      (node (ref "R1") (pin "2") (pinfunction "2_2") (pintype "passive"))
    )
    (net (code "12") (name "Net-(IC1-P3.7{slash}UDM)") (class "Default")
      (node (ref "IC1") (pin "13") (pinfunction "P3.7/UDM_13") (pintype "bidirectional"))
      (node (ref "J1") (pin "2") (pinfunction "D-_2") (pintype "bidirectional"))
    )
    (net (code "13") (name "Net-(IC1-VCC)") (class "Default")
      (node (ref "C1") (pin "1") (pinfunction "1_1") (pintype "passive"))
      (node (ref "IC1") (pin "15") (pinfunction "VCC_15") (pintype "bidirectional"))
      (node (ref "VCC_MCU") (pin "1") (pinfunction "1_1") (pintype "passive"))
    )
    (net (code "14") (name "Net-(PWR-P$2)") (class "Default")
      (node (ref "PWR") (pin "2") (pinfunction "P$2_2") (pintype "passive"))
      (node (ref "Q1") (pin "1") (pinfunction "G_1") (pintype "passive"))
      (node (ref "Q2") (pin "3") (pinfunction "D_3") (pintype "bidirectional"))
      (node (ref "R8") (pin "1") (pinfunction "1_1") (pintype "passive"))
    )
    (net (code "15") (name "Net-(STATUS-DI)") (class "Default")
      (node (ref "STATUS") (pin "DIN") (pinfunction "DI_DIN") (pintype "bidirectional"))
      (node (ref "U$45") (pin "DOUT") (pinfunction "DO_DOUT") (pintype "bidirectional"))
    )
    (net (code "16") (name "Net-(U$1-DI)") (class "Default")
      (node (ref "DIN") (pin "2") (pinfunction "2_2") (pintype "passive"))
      (node (ref "U$1") (pin "DIN") (pinfunction "DI_DIN") (pintype "bidirectional"))
    )
    (net (code "17") (name "Net-(U$1-DO)") (class "Default")
      (node (ref "U$1") (pin "DOUT") (pinfunction "DO_DOUT") (pintype "bidirectional"))
      (node (ref "U$2") (pin "DIN") (pinfunction "DI_DIN") (pintype "bidirectional"))
    )
    (net (code "18") (name "Net-(U$2-DO)") (class "Default")
      (node (ref "U$2") (pin "DOUT") (pinfunction "DO_DOUT") (pintype "bidirectional"))
      (node (ref "U$3") (pin "DIN") (pinfunction "DI_DIN") (pintype "bidirectional"))
    )
    (net (code "19") (name "Net-(U$3-DO)") (class "Default")
      (node (ref "U$3") (pin "DOUT") (pinfunction "DO_DOUT") (pintype "bidirectional"))
      (node (ref "U$4") (pin "DIN") (pinfunction "DI_DIN") (pintype "bidirectional"))
    )
    (net (code "20") (name "Net-(U$4-DO)") (class "Default")
      (node (ref "U$4") (pin "DOUT") (pinfunction "DO_DOUT") (pintype "bidirectional"))
      (node (ref "U$5") (pin "DIN") (pinfunction "DI_DIN") (pintype "bidirectional"))
    )
    (net (code "21") (name "Net-(U$5-DO)") (class "Default")
      (node (ref "U$5") (pin "DOUT") (pinfunction "DO_DOUT") (pintype "bidirectional"))
      (node (ref "U$6") (pin "DIN") (pinfunction "DI_DIN") (pintype "bidirectional"))
    )
    (net (code "22") (name "Net-(U$6-DO)") (class "Default")
      (node (ref "U$6") (pin "DOUT") (pinfunction "DO_DOUT") (pintype "bidirectional"))
      (node (ref "U$7") (pin "DIN") (pinfunction "DI_DIN") (pintype "bidirectional"))
    )
    (net (code "23") (name "Net-(U$7-DO)") (class "Default")
      (node (ref "U$7") (pin "DOUT") (pinfunction "DO_DOUT") (pintype "bidirectional"))
      (node (ref "U$8") (pin "DIN") (pinfunction "DI_DIN") (pintype "bidirectional"))
    )
    (net (code "24") (name "Net-(U$8-DO)") (class "Default")
      (node (ref "U$8") (pin "DOUT") (pinfunction "DO_DOUT") (pintype "bidirectional"))
      (node (ref "U$9") (pin "DIN") (pinfunction "DI_DIN") (pintype "bidirectional"))
    )
    (net (code "25") (name "Net-(U$10-DI)") (class "Default")
      (node (ref "U$10") (pin "DIN") (pinfunction "DI_DIN") (pintype "bidirectional"))
      (node (ref "U$9") (pin "DOUT") (pinfunction "DO_DOUT") (pintype "bidirectional"))
    )
    (net (code "26") (name "Net-(U$10-DO)") (class "Default")
      (node (ref "U$10") (pin "DOUT") (pinfunction "DO_DOUT") (pintype "bidirectional"))
      (node (ref "U$11") (pin "DIN") (pinfunction "DI_DIN") (pintype "bidirectional"))
    )
    (net (code "27") (name "Net-(U$11-DO)") (class "Default")
      (node (ref "U$11") (pin "DOUT") (pinfunction "DO_DOUT") (pintype "bidirectional"))
      (node (ref "U$12") (pin "DIN") (pinfunction "DI_DIN") (pintype "bidirectional"))
    )
    (net (code "28") (name "Net-(U$12-DO)") (class "Default")
      (node (ref "U$12") (pin "DOUT") (pinfunction "DO_DOUT") (pintype "bidirectional"))
      (node (ref "U$13") (pin "DIN") (pinfunction "DI_DIN") (pintype "bidirectional"))
    )
    (net (code "29") (name "Net-(U$13-DO)") (class "Default")
      (node (ref "U$13") (pin "DOUT") (pinfunction "DO_DOUT") (pintype "bidirectional"))
      (node (ref "U$14") (pin "DIN") (pinfunction "DI_DIN") (pintype "bidirectional"))
    )
    (net (code "30") (name "Net-(U$14-DO)") (class "Default")
      (node (ref "U$14") (pin "DOUT") (pinfunction "DO_DOUT") (pintype "bidirectional"))
      (node (ref "U$15") (pin "DIN") (pinfunction "DI_DIN") (pintype "bidirectional"))
    )
    (net (code "31") (name "Net-(U$15-DO)") (class "Default")
      (node (ref "U$15") (pin "DOUT") (pinfunction "DO_DOUT") (pintype "bidirectional"))
      (node (ref "U$16") (pin "DIN") (pinfunction "DI_DIN") (pintype "bidirectional"))
    )
    (net (code "32") (name "Net-(U$16-DO)") (class "Default")
      (node (ref "U$16") (pin "DOUT") (pinfunction "DO_DOUT") (pintype "bidirectional"))
      (node (ref "U$17") (pin "DIN") (pinfunction "DI_DIN") (pintype "bidirectional"))
    )
    (net (code "33") (name "Net-(U$17-DO)") (class "Default")
      (node (ref "U$17") (pin "DOUT") (pinfunction "DO_DOUT") (pintype "bidirectional"))
      (node (ref "U$18") (pin "DIN") (pinfunction "DI_DIN") (pintype "bidirectional"))
    )
    (net (code "34") (name "Net-(U$18-DO)") (class "Default")
      (node (ref "U$18") (pin "DOUT") (pinfunction "DO_DOUT") (pintype "bidirectional"))
      (node (ref "U$19") (pin "DIN") (pinfunction "DI_DIN") (pintype "bidirectional"))
    )
    (net (code "35") (name "Net-(U$19-DO)") (class "Default")
      (node (ref "U$19") (pin "DOUT") (pinfunction "DO_DOUT") (pintype "bidirectional"))
      (node (ref "U$20") (pin "DIN") (pinfunction "DI_DIN") (pintype "bidirectional"))
    )
    (net (code "36") (name "Net-(U$20-DO)") (class "Default")
      (node (ref "U$20") (pin "DOUT") (pinfunction "DO_DOUT") (pintype "bidirectional"))
      (node (ref "U$21") (pin "DIN") (pinfunction "DI_DIN") (pintype "bidirectional"))
    )
    (net (code "37") (name "Net-(U$21-DO)") (class "Default")
      (node (ref "U$21") (pin "DOUT") (pinfunction "DO_DOUT") (pintype "bidirectional"))
      (node (ref "U$22") (pin "DIN") (pinfunction "DI_DIN") (pintype "bidirectional"))
    )
    (net (code "38") (name "Net-(U$22-DO)") (class "Default")
      (node (ref "U$22") (pin "DOUT") (pinfunction "DO_DOUT") (pintype "bidirectional"))
      (node (ref "U$23") (pin "DIN") (pinfunction "DI_DIN") (pintype "bidirectional"))
    )
    (net (code "39") (name "Net-(U$23-DO)") (class "Default")
      (node (ref "U$23") (pin "DOUT") (pinfunction "DO_DOUT") (pintype "bidirectional"))
      (node (ref "U$24") (pin "DIN") (pinfunction "DI_DIN") (pintype "bidirectional"))
    )
    (net (code "40") (name "Net-(U$24-DO)") (class "Default")
      (node (ref "U$24") (pin "DOUT") (pinfunction "DO_DOUT") (pintype "bidirectional"))
      (node (ref "U$25") (pin "DIN") (pinfunction "DI_DIN") (pintype "bidirectional"))
    )
    (net (code "41") (name "Net-(U$25-DO)") (class "Default")
      (node (ref "U$25") (pin "DOUT") (pinfunction "DO_DOUT") (pintype "bidirectional"))
      (node (ref "U$26") (pin "DIN") (pinfunction "DI_DIN") (pintype "bidirectional"))
    )
    (net (code "42") (name "Net-(U$26-DO)") (class "Default")
      (node (ref "U$26") (pin "DOUT") (pinfunction "DO_DOUT") (pintype "bidirectional"))
      (node (ref "U$27") (pin "DIN") (pinfunction "DI_DIN") (pintype "bidirectional"))
    )
    (net (code "43") (name "Net-(U$27-DO)") (class "Default")
      (node (ref "U$27") (pin "DOUT") (pinfunction "DO_DOUT") (pintype "bidirectional"))
      (node (ref "U$28") (pin "DIN") (pinfunction "DI_DIN") (pintype "bidirectional"))
    )
    (net (code "44") (name "Net-(U$28-DO)") (class "Default")
      (node (ref "U$28") (pin "DOUT") (pinfunction "DO_DOUT") (pintype "bidirectional"))
      (node (ref "U$29") (pin "DIN") (pinfunction "DI_DIN") (pintype "bidirectional"))
    )
    (net (code "45") (name "Net-(U$29-DO)") (class "Default")
      (node (ref "U$29") (pin "DOUT") (pinfunction "DO_DOUT") (pintype "bidirectional"))
      (node (ref "U$30") (pin "DIN") (pinfunction "DI_DIN") (pintype "bidirectional"))
    )
    (net (code "46") (name "Net-(U$30-DO)") (class "Default")
      (node (ref "U$30") (pin "DOUT") (pinfunction "DO_DOUT") (pintype "bidirectional"))
      (node (ref "U$31") (pin "DIN") (pinfunction "DI_DIN") (pintype "bidirectional"))
    )
    (net (code "47") (name "Net-(U$31-DO)") (class "Default")
      (node (ref "U$31") (pin "DOUT") (pinfunction "DO_DOUT") (pintype "bidirectional"))
      (node (ref "U$32") (pin "DIN") (pinfunction "DI_DIN") (pintype "bidirectional"))
    )
    (net (code "48") (name "Net-(U$32-DO)") (class "Default")
      (node (ref "U$32") (pin "DOUT") (pinfunction "DO_DOUT") (pintype "bidirectional"))
      (node (ref "U$33") (pin "DIN") (pinfunction "DI_DIN") (pintype "bidirectional"))
    )
    (net (code "49") (name "Net-(U$33-DO)") (class "Default")
      (node (ref "U$33") (pin "DOUT") (pinfunction "DO_DOUT") (pintype "bidirectional"))
      (node (ref "U$34") (pin "DIN") (pinfunction "DI_DIN") (pintype "bidirectional"))
    )
    (net (code "50") (name "Net-(U$34-DO)") (class "Default")
      (node (ref "U$34") (pin "DOUT") (pinfunction "DO_DOUT") (pintype "bidirectional"))
      (node (ref "U$35") (pin "DIN") (pinfunction "DI_DIN") (pintype "bidirectional"))
    )
    (net (code "51") (name "Net-(U$35-DO)") (class "Default")
      (node (ref "U$35") (pin "DOUT") (pinfunction "DO_DOUT") (pintype "bidirectional"))
      (node (ref "U$36") (pin "DIN") (pinfunction "DI_DIN") (pintype "bidirectional"))
    )
    (net (code "52") (name "Net-(U$36-DO)") (class "Default")
      (node (ref "U$36") (pin "DOUT") (pinfunction "DO_DOUT") (pintype "bidirectional"))
      (node (ref "U$37") (pin "DIN") (pinfunction "DI_DIN") (pintype "bidirectional"))
    )
    (net (code "53") (name "Net-(U$37-DO)") (class "Default")
      (node (ref "U$37") (pin "DOUT") (pinfunction "DO_DOUT") (pintype "bidirectional"))
      (node (ref "U$38") (pin "DIN") (pinfunction "DI_DIN") (pintype "bidirectional"))
    )
    (net (code "54") (name "Net-(U$38-DO)") (class "Default")
      (node (ref "U$38") (pin "DOUT") (pinfunction "DO_DOUT") (pintype "bidirectional"))
      (node (ref "U$39") (pin "DIN") (pinfunction "DI_DIN") (pintype "bidirectional"))
    )
    (net (code "55") (name "Net-(U$39-DO)") (class "Default")
      (node (ref "U$39") (pin "DOUT") (pinfunction "DO_DOUT") (pintype "bidirectional"))
      (node (ref "U$40") (pin "DIN") (pinfunction "DI_DIN") (pintype "bidirectional"))
    )
    (net (code "56") (name "Net-(U$40-DO)") (class "Default")
      (node (ref "U$40") (pin "DOUT") (pinfunction "DO_DOUT") (pintype "bidirectional"))
      (node (ref "U$41") (pin "DIN") (pinfunction "DI_DIN") (pintype "bidirectional"))
    )
    (net (code "57") (name "Net-(U$41-DO)") (class "Default")
      (node (ref "U$41") (pin "DOUT") (pinfunction "DO_DOUT") (pintype "bidirectional"))
      (node (ref "U$42") (pin "DIN") (pinfunction "DI_DIN") (pintype "bidirectional"))
    )
    (net (code "58") (name "Net-(U$42-DO)") (class "Default")
      (node (ref "U$42") (pin "DOUT") (pinfunction "DO_DOUT") (pintype "bidirectional"))
      (node (ref "U$43") (pin "DIN") (pinfunction "DI_DIN") (pintype "bidirectional"))
    )
    (net (code "59") (name "Net-(U$43-DO)") (class "Default")
      (node (ref "U$43") (pin "DOUT") (pinfunction "DO_DOUT") (pintype "bidirectional"))
      (node (ref "U$44") (pin "DIN") (pinfunction "DI_DIN") (pintype "bidirectional"))
    )
    (net (code "60") (name "Net-(U$44-DO)") (class "Default")
      (node (ref "U$44") (pin "DOUT") (pinfunction "DO_DOUT") (pintype "bidirectional"))
      (node (ref "U$45") (pin "DIN") (pinfunction "DI_DIN") (pintype "bidirectional"))
    )
    (net (code "61") (name "Net-(U1-PROG)") (class "Default")
      (node (ref "R2") (pin "1") (pinfunction "1_1") (pintype "passive"))
      (node (ref "U1") (pin "5") (pinfunction "PROG_5") (pintype "input"))
    )
    (net (code "62") (name "Net-(U2-FB)") (class "Default")
      (node (ref "R3") (pin "1") (pinfunction "1_1") (pintype "passive"))
      (node (ref "R4") (pin "2") (pinfunction "2_2") (pintype "passive"))
      (node (ref "U2") (pin "3") (pinfunction "FB_3") (pintype "bidirectional"))
    )
    (net (code "63") (name "Net-(U2-SW)") (class "Default")
      (node (ref "D1") (pin "A") (pinfunction "A_A") (pintype "passive"))
      (node (ref "L1") (pin "2") (pinfunction "2_2") (pintype "passive"))
      (node (ref "U2") (pin "1") (pinfunction "SW_1") (pintype "bidirectional"))
    )
    (net (code "64") (name "P1.6") (class "Default")
      (node (ref "DP-") (pin "1") (pinfunction "P$1_1") (pintype "bidirectional"))
      (node (ref "DP-") (pin "2") (pinfunction "P$1_2") (pintype "bidirectional"))
      (node (ref "EP-") (pin "1") (pinfunction "P$1_1") (pintype "bidirectional"))
      (node (ref "EP-") (pin "2") (pinfunction "P$1_2") (pintype "bidirectional"))
      (node (ref "HP-") (pin "1") (pinfunction "P$1_1") (pintype "bidirectional"))
      (node (ref "HP-") (pin "2") (pinfunction "P$1_2") (pintype "bidirectional"))
      (node (ref "IC1") (pin "4") (pinfunction "P1.6/MISO/RXD1/TIN4_4") (pintype "bidirectional"))
    )
    (net (code "65") (name "P1.7") (class "Default")
      (node (ref "DP+") (pin "1") (pinfunction "P$1_1") (pintype "bidirectional"))
      (node (ref "DP+") (pin "2") (pinfunction "P$1_2") (pintype "bidirectional"))
      (node (ref "EP+") (pin "1") (pinfunction "P$1_1") (pintype "bidirectional"))
      (node (ref "EP+") (pin "2") (pinfunction "P$1_2") (pintype "bidirectional"))
      (node (ref "HP+") (pin "1") (pinfunction "P$1_1") (pintype "bidirectional"))
      (node (ref "HP+") (pin "2") (pinfunction "P$1_2") (pintype "bidirectional"))
      (node (ref "IC1") (pin "5") (pinfunction "P1.7/SCK/TXD1/TIN5_5") (pintype "bidirectional"))
    )
    (net (code "66") (name "P3.0") (class "Default")
      (node (ref "HP+") (pin "3") (pinfunction "P$2_3") (pintype "bidirectional"))
      (node (ref "HP+") (pin "4") (pinfunction "P$2_4") (pintype "bidirectional"))
      (node (ref "HP-") (pin "3") (pinfunction "P$2_3") (pintype "bidirectional"))
      (node (ref "HP-") (pin "4") (pinfunction "P$2_4") (pintype "bidirectional"))
      (node (ref "IC1") (pin "8") (pinfunction "P3.0/PWM1_/RXD_8") (pintype "bidirectional"))
    )
    (net (code "67") (name "P3.1") (class "Default")
      (node (ref "EP+") (pin "3") (pinfunction "P$2_3") (pintype "bidirectional"))
      (node (ref "EP+") (pin "4") (pinfunction "P$2_4") (pintype "bidirectional"))
      (node (ref "EP-") (pin "3") (pinfunction "P$2_3") (pintype "bidirectional"))
      (node (ref "EP-") (pin "4") (pinfunction "P$2_4") (pintype "bidirectional"))
      (node (ref "IC1") (pin "7") (pinfunction "P3.1/PWM2_/TXD_7") (pintype "bidirectional"))
    )
    (net (code "68") (name "P3.3") (class "Default")
      (node (ref "DP+") (pin "3") (pinfunction "P$2_3") (pintype "bidirectional"))
      (node (ref "DP+") (pin "4") (pinfunction "P$2_4") (pintype "bidirectional"))
      (node (ref "DP-") (pin "3") (pinfunction "P$2_3") (pintype "bidirectional"))
      (node (ref "DP-") (pin "4") (pinfunction "P$2_4") (pintype "bidirectional"))
      (node (ref "IC1") (pin "10") (pinfunction "P3.3/INT1_10") (pintype "bidirectional"))
    )
    (net (code "69") (name "P3.4") (class "Default")
      (node (ref "IC1") (pin "11") (pinfunction "P3.4/PWM2/RXD1_/T0_11") (pintype "bidirectional"))
      (node (ref "U1") (pin "1") (pinfunction "STAT_1") (pintype "output"))
    )
    (net (code "70") (name "RST") (class "Default")
      (node (ref "IC1") (pin "6") (pinfunction "RST/T2EX_/CAP2__6") (pintype "bidirectional"))
    )
    (net (code "71") (name "TIN1") (class "Default")
      (node (ref "R5") (pin "2") (pinfunction "2_2") (pintype "passive"))
      (node (ref "TIN1") (pin "P$1") (pinfunction "P$1_P$1") (pintype "bidirectional"))
    )
    (net (code "72") (name "TIN2") (class "Default")
      (node (ref "R6") (pin "1") (pinfunction "1_1") (pintype "passive"))
      (node (ref "TIN2") (pin "P$1") (pinfunction "P$1_P$1") (pintype "bidirectional"))
    )
    (net (code "73") (name "VBAT") (class "Default")
      (node (ref "C3") (pin "1") (pinfunction "1_1") (pintype "passive"))
      (node (ref "PTC1") (pin "1") (pinfunction "1_1") (pintype "passive"))
      (node (ref "Q1") (pin "2") (pinfunction "S_2") (pintype "passive"))
      (node (ref "R8") (pin "2") (pinfunction "2_2") (pintype "passive"))
      (node (ref "U1") (pin "3") (pinfunction "VBAT_3") (pintype "power_in"))
    )
    (net (code "74") (name "VBUS5V") (class "Default")
      (node (ref "C4") (pin "1") (pinfunction "1_1") (pintype "passive"))
      (node (ref "J1") (pin "1") (pinfunction "VBUS_1") (pintype "power_in"))
      (node (ref "Q2") (pin "1") (pinfunction "G_1") (pintype "bidirectional"))
      (node (ref "R7") (pin "2") (pinfunction "2_2") (pintype "passive"))
      (node (ref "U1") (pin "4") (pinfunction "VIN_4") (pintype "power_in"))
    )
    (net (code "75") (name "VCC") (class "Default")
      (node (ref "BOOT") (pin "3") (pinfunction "P$2_3") (pintype "bidirectional"))
      (node (ref "BOOT") (pin "4") (pinfunction "P$2_4") (pintype "bidirectional"))
      (node (ref "C5") (pin "1") (pinfunction "1_1") (pintype "passive"))
      (node (ref "D1") (pin "C") (pinfunction "C_C") (pintype "passive"))
      (node (ref "R3") (pin "2") (pinfunction "2_2") (pintype "passive"))
      (node (ref "STATUS") (pin "VDD") (pinfunction "VDD_VDD") (pintype "bidirectional"))
      (node (ref "U$1") (pin "VDD") (pinfunction "VDD_VDD") (pintype "bidirectional"))
      (node (ref "U$10") (pin "VDD") (pinfunction "VDD_VDD") (pintype "bidirectional"))
      (node (ref "U$11") (pin "VDD") (pinfunction "VDD_VDD") (pintype "bidirectional"))
      (node (ref "U$12") (pin "VDD") (pinfunction "VDD_VDD") (pintype "bidirectional"))
      (node (ref "U$13") (pin "VDD") (pinfunction "VDD_VDD") (pintype "bidirectional"))
      (node (ref "U$14") (pin "VDD") (pinfunction "VDD_VDD") (pintype "bidirectional"))
      (node (ref "U$15") (pin "VDD") (pinfunction "VDD_VDD") (pintype "bidirectional"))
      (node (ref "U$16") (pin "VDD") (pinfunction "VDD_VDD") (pintype "bidirectional"))
      (node (ref "U$17") (pin "VDD") (pinfunction "VDD_VDD") (pintype "bidirectional"))
      (node (ref "U$18") (pin "VDD") (pinfunction "VDD_VDD") (pintype "bidirectional"))
      (node (ref "U$19") (pin "VDD") (pinfunction "VDD_VDD") (pintype "bidirectional"))
      (node (ref "U$2") (pin "VDD") (pinfunction "VDD_VDD") (pintype "bidirectional"))
      (node (ref "U$20") (pin "VDD") (pinfunction "VDD_VDD") (pintype "bidirectional"))
      (node (ref "U$21") (pin "VDD") (pinfunction "VDD_VDD") (pintype "bidirectional"))
      (node (ref "U$22") (pin "VDD") (pinfunction "VDD_VDD") (pintype "bidirectional"))
      (node (ref "U$23") (pin "VDD") (pinfunction "VDD_VDD") (pintype "bidirectional"))
      (node (ref "U$24") (pin "VDD") (pinfunction "VDD_VDD") (pintype "bidirectional"))
      (node (ref "U$25") (pin "VDD") (pinfunction "VDD_VDD") (pintype "bidirectional"))
      (node (ref "U$26") (pin "VDD") (pinfunction "VDD_VDD") (pintype "bidirectional"))
      (node (ref "U$27") (pin "VDD") (pinfunction "VDD_VDD") (pintype "bidirectional"))
      (node (ref "U$28") (pin "VDD") (pinfunction "VDD_VDD") (pintype "bidirectional"))
      (node (ref "U$29") (pin "VDD") (pinfunction "VDD_VDD") (pintype "bidirectional"))
      (node (ref "U$3") (pin "VDD") (pinfunction "VDD_VDD") (pintype "bidirectional"))
      (node (ref "U$30") (pin "VDD") (pinfunction "VDD_VDD") (pintype "bidirectional"))
      (node (ref "U$31") (pin "VDD") (pinfunction "VDD_VDD") (pintype "bidirectional"))
      (node (ref "U$32") (pin "VDD") (pinfunction "VDD_VDD") (pintype "bidirectional"))
      (node (ref "U$33") (pin "VDD") (pinfunction "VDD_VDD") (pintype "bidirectional"))
      (node (ref "U$34") (pin "VDD") (pinfunction "VDD_VDD") (pintype "bidirectional"))
      (node (ref "U$35") (pin "VDD") (pinfunction "VDD_VDD") (pintype "bidirectional"))
      (node (ref "U$36") (pin "VDD") (pinfunction "VDD_VDD") (pintype "bidirectional"))
      (node (ref "U$37") (pin "VDD") (pinfunction "VDD_VDD") (pintype "bidirectional"))
      (node (ref "U$38") (pin "VDD") (pinfunction "VDD_VDD") (pintype "bidirectional"))
      (node (ref "U$39") (pin "VDD") (pinfunction "VDD_VDD") (pintype "bidirectional"))
      (node (ref "U$4") (pin "VDD") (pinfunction "VDD_VDD") (pintype "bidirectional"))
      (node (ref "U$40") (pin "VDD") (pinfunction "VDD_VDD") (pintype "bidirectional"))
      (node (ref "U$41") (pin "VDD") (pinfunction "VDD_VDD") (pintype "bidirectional"))
      (node (ref "U$42") (pin "VDD") (pinfunction "VDD_VDD") (pintype "bidirectional"))
      (node (ref "U$43") (pin "VDD") (pinfunction "VDD_VDD") (pintype "bidirectional"))
      (node (ref "U$44") (pin "VDD") (pinfunction "VDD_VDD") (pintype "bidirectional"))
      (node (ref "U$45") (pin "VDD") (pinfunction "VDD_VDD") (pintype "bidirectional"))
      (node (ref "U$5") (pin "VDD") (pinfunction "VDD_VDD") (pintype "bidirectional"))
      (node (ref "U$6") (pin "VDD") (pinfunction "VDD_VDD") (pintype "bidirectional"))
      (node (ref "U$7") (pin "VDD") (pinfunction "VDD_VDD") (pintype "bidirectional"))
      (node (ref "U$8") (pin "VDD") (pinfunction "VDD_VDD") (pintype "bidirectional"))
      (node (ref "U$9") (pin "VDD") (pinfunction "VDD_VDD") (pintype "bidirectional"))
      (node (ref "VCC_MCU") (pin "2") (pinfunction "2_2") (pintype "passive"))
    )
    (net (code "76") (name "unconnected-(J1-ID-Pad4)") (class "Default")
      (node (ref "J1") (pin "4") (pinfunction "ID_4") (pintype "bidirectional"))
    )
    (net (code "77") (name "unconnected-(PWR-P$1-Pad1)") (class "Default")
      (node (ref "PWR") (pin "1") (pinfunction "P$1_1") (pintype "passive"))
    )
  )
)
